# H3_MIDIController_Rev_3_PZBoard.net
KiCad netlist of a schematic drawn in EAGLE
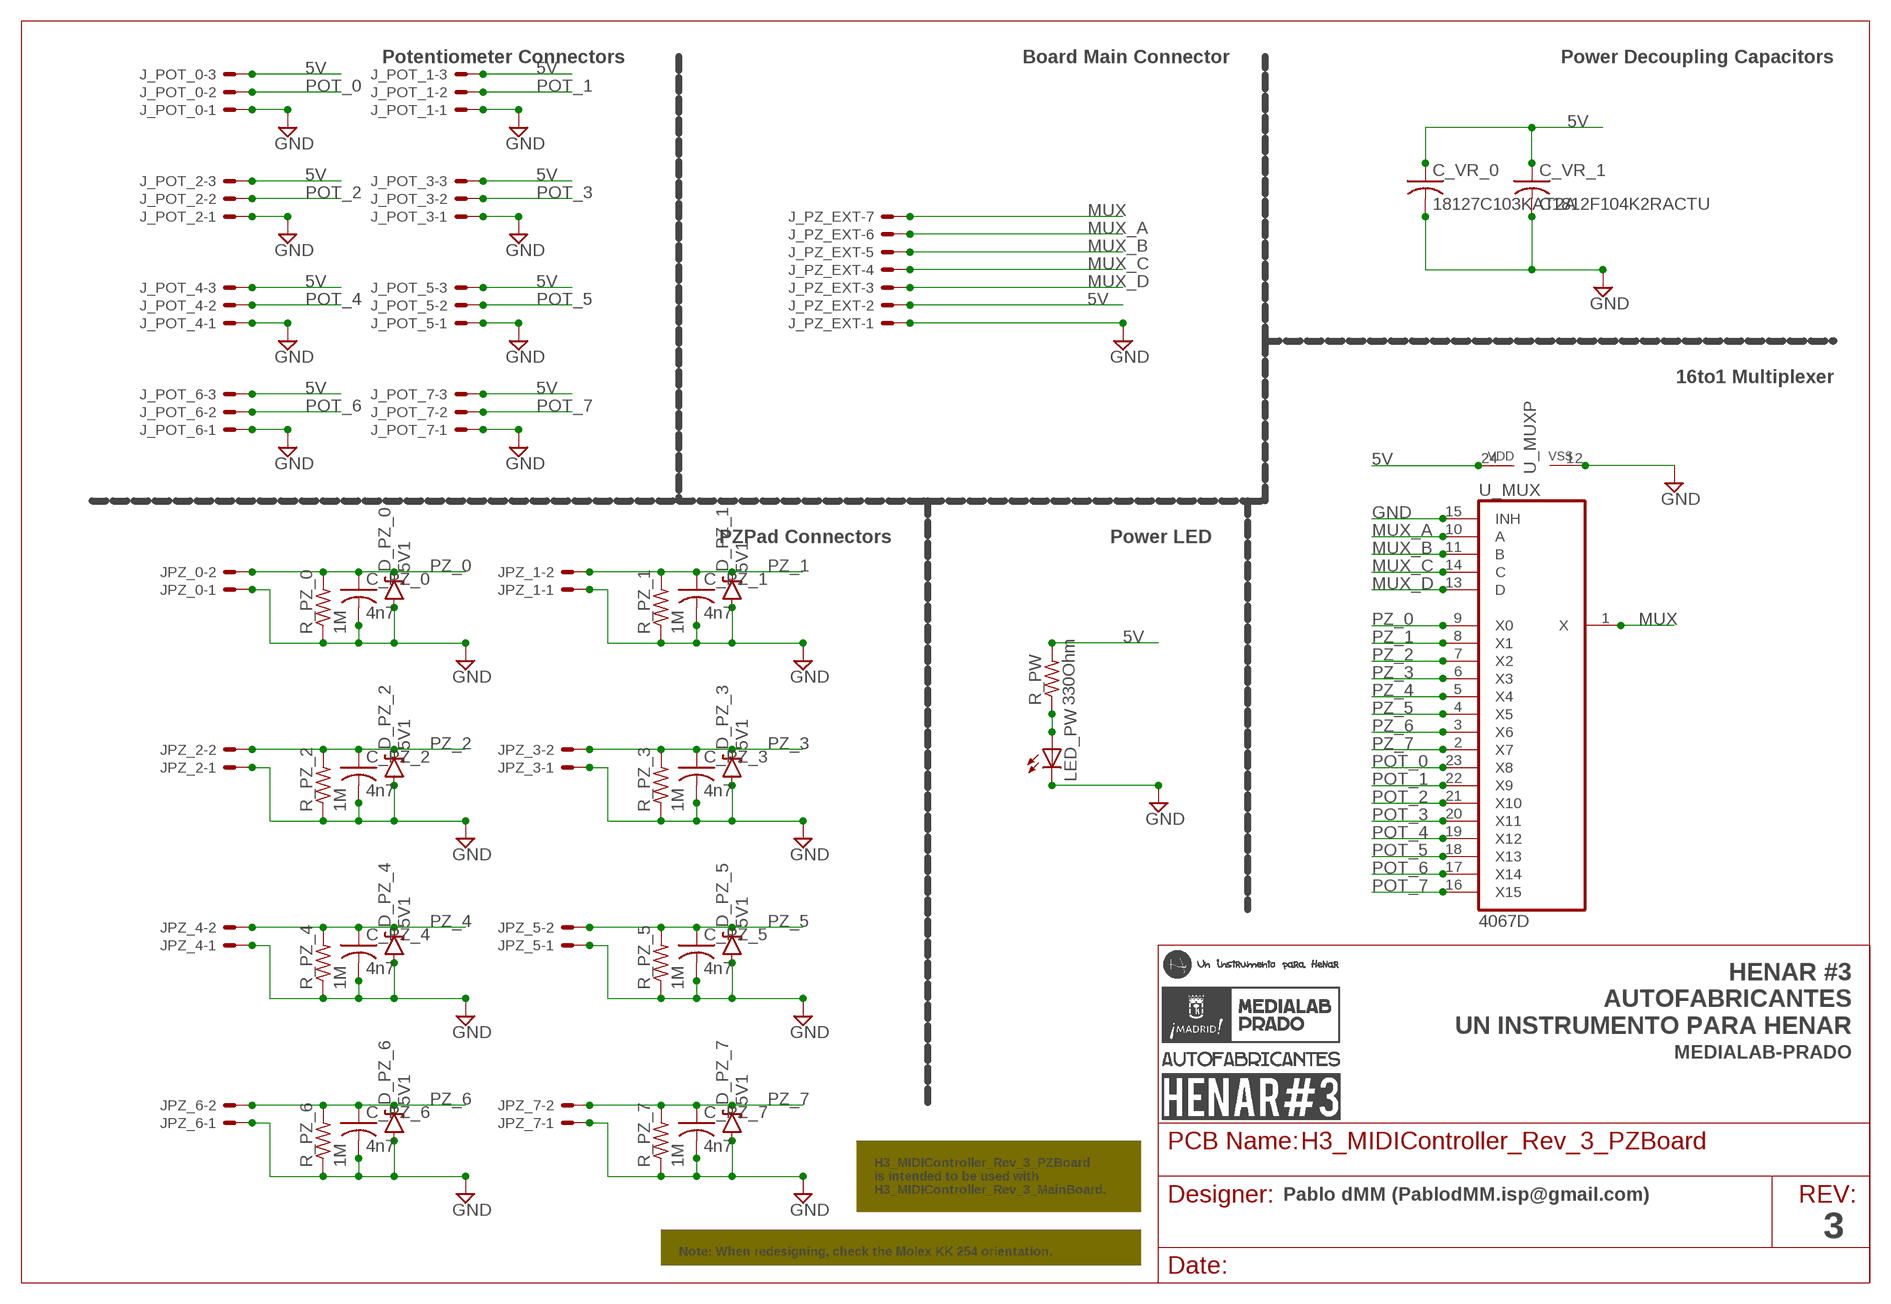
[diagram p0: schematic, sheet 1]

(export (version "E")
  (design (tool "Eeschema 10.0.6"))
  (components
    (comp (ref "C_PZ_0")
      (value "4n7")
      (footprint "eagle-import:C1206")
      (libsource (lib "eagle-import") (part "C-USC1206"))
    )
    (comp (ref "C_PZ_1")
      (value "4n7")
      (footprint "eagle-import:C1206")
      (libsource (lib "eagle-import") (part "C-USC1206"))
    )
    (comp (ref "C_PZ_2")
      (value "4n7")
      (footprint "eagle-import:C1206")
      (libsource (lib "eagle-import") (part "C-USC1206"))
    )
    (comp (ref "C_PZ_3")
      (value "4n7")
      (footprint "eagle-import:C1206")
      (libsource (lib "eagle-import") (part "C-USC1206"))
    )
    (comp (ref "C_PZ_4")
      (value "4n7")
      (footprint "eagle-import:C1206")
      (libsource (lib "eagle-import") (part "C-USC1206"))
    )
    (comp (ref "C_PZ_5")
      (value "4n7")
      (footprint "eagle-import:C1206")
      (libsource (lib "eagle-import") (part "C-USC1206"))
    )
    (comp (ref "C_PZ_6")
      (value "4n7")
      (footprint "eagle-import:C1206")
      (libsource (lib "eagle-import") (part "C-USC1206"))
    )
    (comp (ref "C_PZ_7")
      (value "4n7")
      (footprint "eagle-import:C1206")
      (libsource (lib "eagle-import") (part "C-USC1206"))
    )
    (comp (ref "C_VR_0")
      (value "18127C103KAT2A")
      (footprint "eagle-import:C1812K")
      (libsource (lib "eagle-import") (part "C-USC1812K"))
    )
    (comp (ref "C_VR_1")
      (value "C1812F104K2RACTU")
      (footprint "eagle-import:C1812K")
      (libsource (lib "eagle-import") (part "C-USC1812K"))
    )
    (comp (ref "D_PZ_0")
      (value "5V1")
      (footprint "eagle-import:DIODE-BZT52")
      (libsource (lib "eagle-import") (part "DIODE-ZENER"))
    )
    (comp (ref "D_PZ_1")
      (value "5V1")
      (footprint "eagle-import:DIODE-BZT52")
      (libsource (lib "eagle-import") (part "DIODE-ZENER"))
    )
    (comp (ref "D_PZ_2")
      (value "5V1")
      (footprint "eagle-import:DIODE-BZT52")
      (libsource (lib "eagle-import") (part "DIODE-ZENER"))
    )
    (comp (ref "D_PZ_3")
      (value "5V1")
      (footprint "eagle-import:DIODE-BZT52")
      (libsource (lib "eagle-import") (part "DIODE-ZENER"))
    )
    (comp (ref "D_PZ_4")
      (value "5V1")
      (footprint "eagle-import:DIODE-BZT52")
      (libsource (lib "eagle-import") (part "DIODE-ZENER"))
    )
    (comp (ref "D_PZ_5")
      (value "5V1")
      (footprint "eagle-import:DIODE-BZT52")
      (libsource (lib "eagle-import") (part "DIODE-ZENER"))
    )
    (comp (ref "D_PZ_6")
      (value "5V1")
      (footprint "eagle-import:DIODE-BZT52")
      (libsource (lib "eagle-import") (part "DIODE-ZENER"))
    )
    (comp (ref "D_PZ_7")
      (value "5V1")
      (footprint "eagle-import:DIODE-BZT52")
      (libsource (lib "eagle-import") (part "DIODE-ZENER"))
    )
    (comp (ref "JPZ_0")
      (value "22-05-7028-02")
      (footprint "eagle-import:7395-02")
      (libsource (lib "eagle-import") (part "22-?-0205-7028"))
    )
    (comp (ref "JPZ_1")
      (value "22-05-7028-02")
      (footprint "eagle-import:7395-02")
      (libsource (lib "eagle-import") (part "22-?-0205-7028"))
    )
    (comp (ref "JPZ_2")
      (value "22-05-7028-02")
      (footprint "eagle-import:7395-02")
      (libsource (lib "eagle-import") (part "22-?-0205-7028"))
    )
    (comp (ref "JPZ_3")
      (value "22-05-7028-02")
      (footprint "eagle-import:7395-02")
      (libsource (lib "eagle-import") (part "22-?-0205-7028"))
    )
    (comp (ref "JPZ_4")
      (value "22-05-7028-02")
      (footprint "eagle-import:7395-02")
      (libsource (lib "eagle-import") (part "22-?-0205-7028"))
    )
    (comp (ref "JPZ_5")
      (value "22-05-7028-02")
      (footprint "eagle-import:7395-02")
      (libsource (lib "eagle-import") (part "22-?-0205-7028"))
    )
    (comp (ref "JPZ_6")
      (value "22-05-7028-02")
      (footprint "eagle-import:7395-02")
      (libsource (lib "eagle-import") (part "22-?-0205-7028"))
    )
    (comp (ref "JPZ_7")
      (value "22-05-7028-02")
      (footprint "eagle-import:7395-02")
      (libsource (lib "eagle-import") (part "22-?-0205-7028"))
    )
    (comp (ref "J_POT_0")
      (value "22-05-7038-03")
      (footprint "eagle-import:7395-03")
      (libsource (lib "eagle-import") (part "22-?-0305-7038"))
    )
    (comp (ref "J_POT_1")
      (value "22-05-7038-03")
      (footprint "eagle-import:7395-03")
      (libsource (lib "eagle-import") (part "22-?-0305-7038"))
    )
    (comp (ref "J_POT_2")
      (value "22-05-7038-03")
      (footprint "eagle-import:7395-03")
      (libsource (lib "eagle-import") (part "22-?-0305-7038"))
    )
    (comp (ref "J_POT_3")
      (value "22-05-7038-03")
      (footprint "eagle-import:7395-03")
      (libsource (lib "eagle-import") (part "22-?-0305-7038"))
    )
    (comp (ref "J_POT_4")
      (value "22-05-7038-03")
      (footprint "eagle-import:7395-03")
      (libsource (lib "eagle-import") (part "22-?-0305-7038"))
    )
    (comp (ref "J_POT_5")
      (value "22-05-7038-03")
      (footprint "eagle-import:7395-03")
      (libsource (lib "eagle-import") (part "22-?-0305-7038"))
    )
    (comp (ref "J_POT_6")
      (value "22-05-7038-03")
      (footprint "eagle-import:7395-03")
      (libsource (lib "eagle-import") (part "22-?-0305-7038"))
    )
    (comp (ref "J_POT_7")
      (value "22-05-7038-03")
      (footprint "eagle-import:7395-03")
      (libsource (lib "eagle-import") (part "22-?-0305-7038"))
    )
    (comp (ref "J_PZ_EXT")
      (value "22-05-7078-07")
      (footprint "eagle-import:7395-07")
      (libsource (lib "eagle-import") (part "22-?-0705-7078"))
    )
    (comp (ref "LED_PW")
      (value "LEDSMT1206")
      (footprint "eagle-import:1206")
      (libsource (lib "eagle-import") (part "LEDSMT1206"))
    )
    (comp (ref "R_PW")
      (value "330Ohm")
      (footprint "eagle-import:M1206")
      (libsource (lib "eagle-import") (part "R-US_M1206"))
    )
    (comp (ref "R_PZ_0")
      (value "1M")
      (footprint "eagle-import:M1206")
      (libsource (lib "eagle-import") (part "R-US_M1206"))
    )
    (comp (ref "R_PZ_1")
      (value "1M")
      (footprint "eagle-import:M1206")
      (libsource (lib "eagle-import") (part "R-US_M1206"))
    )
    (comp (ref "R_PZ_2")
      (value "1M")
      (footprint "eagle-import:M1206")
      (libsource (lib "eagle-import") (part "R-US_M1206"))
    )
    (comp (ref "R_PZ_3")
      (value "1M")
      (footprint "eagle-import:M1206")
      (libsource (lib "eagle-import") (part "R-US_M1206"))
    )
    (comp (ref "R_PZ_4")
      (value "1M")
      (footprint "eagle-import:M1206")
      (libsource (lib "eagle-import") (part "R-US_M1206"))
    )
    (comp (ref "R_PZ_5")
      (value "1M")
      (footprint "eagle-import:M1206")
      (libsource (lib "eagle-import") (part "R-US_M1206"))
    )
    (comp (ref "R_PZ_6")
      (value "1M")
      (footprint "eagle-import:M1206")
      (libsource (lib "eagle-import") (part "R-US_M1206"))
    )
    (comp (ref "R_PZ_7")
      (value "1M")
      (footprint "eagle-import:M1206")
      (libsource (lib "eagle-import") (part "R-US_M1206"))
    )
    (comp (ref "U_MUX")
      (value "4067D")
      (footprint "eagle-import:SO24W")
      (libsource (lib "eagle-import") (part "4067D"))
    )
  )
  (nets
    (net (code "1") (name "/5V") (class "Default")
      (node (ref "C_VR_0") (pin "1") (pinfunction "1_1") (pintype "passive"))
      (node (ref "C_VR_1") (pin "1") (pinfunction "1_1") (pintype "passive"))
      (node (ref "J_POT_0") (pin "3") (pinfunction "S_3") (pintype "passive"))
      (node (ref "J_POT_1") (pin "3") (pinfunction "S_3") (pintype "passive"))
      (node (ref "J_POT_2") (pin "3") (pinfunction "S_3") (pintype "passive"))
      (node (ref "J_POT_3") (pin "3") (pinfunction "S_3") (pintype "passive"))
      (node (ref "J_POT_4") (pin "3") (pinfunction "S_3") (pintype "passive"))
      (node (ref "J_POT_5") (pin "3") (pinfunction "S_3") (pintype "passive"))
      (node (ref "J_POT_6") (pin "3") (pinfunction "S_3") (pintype "passive"))
      (node (ref "J_POT_7") (pin "3") (pinfunction "S_3") (pintype "passive"))
      (node (ref "J_PZ_EXT") (pin "2") (pinfunction "S_2") (pintype "passive"))
      (node (ref "R_PW") (pin "2") (pinfunction "2_2") (pintype "passive"))
      (node (ref "U_MUX") (pin "24") (pinfunction "VDD_24") (pintype "power_in"))
    )
    (net (code "2") (name "/MUX") (class "Default")
      (node (ref "J_PZ_EXT") (pin "7") (pinfunction "S_7") (pintype "passive"))
      (node (ref "U_MUX") (pin "1") (pinfunction "X_1") (pintype "output"))
    )
    (net (code "3") (name "/MUX_A") (class "Default")
      (node (ref "J_PZ_EXT") (pin "6") (pinfunction "S_6") (pintype "passive"))
      (node (ref "U_MUX") (pin "10") (pinfunction "A_10") (pintype "input"))
    )
    (net (code "4") (name "/MUX_B") (class "Default")
      (node (ref "J_PZ_EXT") (pin "5") (pinfunction "S_5") (pintype "passive"))
      (node (ref "U_MUX") (pin "11") (pinfunction "B_11") (pintype "input"))
    )
    (net (code "5") (name "/MUX_C") (class "Default")
      (node (ref "J_PZ_EXT") (pin "4") (pinfunction "S_4") (pintype "passive"))
      (node (ref "U_MUX") (pin "14") (pinfunction "C_14") (pintype "input"))
    )
    (net (code "6") (name "/MUX_D") (class "Default")
      (node (ref "J_PZ_EXT") (pin "3") (pinfunction "S_3") (pintype "passive"))
      (node (ref "U_MUX") (pin "13") (pinfunction "D_13") (pintype "input"))
    )
    (net (code "7") (name "/POT_0") (class "Default")
      (node (ref "J_POT_0") (pin "2") (pinfunction "S_2") (pintype "passive"))
      (node (ref "U_MUX") (pin "23") (pinfunction "X8_23") (pintype "input"))
    )
    (net (code "8") (name "/POT_1") (class "Default")
      (node (ref "J_POT_1") (pin "2") (pinfunction "S_2") (pintype "passive"))
      (node (ref "U_MUX") (pin "22") (pinfunction "X9_22") (pintype "input"))
    )
    (net (code "9") (name "/POT_2") (class "Default")
      (node (ref "J_POT_2") (pin "2") (pinfunction "S_2") (pintype "passive"))
      (node (ref "U_MUX") (pin "21") (pinfunction "X10_21") (pintype "input"))
    )
    (net (code "10") (name "/POT_3") (class "Default")
      (node (ref "J_POT_3") (pin "2") (pinfunction "S_2") (pintype "passive"))
      (node (ref "U_MUX") (pin "20") (pinfunction "X11_20") (pintype "input"))
    )
    (net (code "11") (name "/POT_4") (class "Default")
      (node (ref "J_POT_4") (pin "2") (pinfunction "S_2") (pintype "passive"))
      (node (ref "U_MUX") (pin "19") (pinfunction "X12_19") (pintype "input"))
    )
    (net (code "12") (name "/POT_5") (class "Default")
      (node (ref "J_POT_5") (pin "2") (pinfunction "S_2") (pintype "passive"))
      (node (ref "U_MUX") (pin "18") (pinfunction "X13_18") (pintype "input"))
    )
    (net (code "13") (name "/POT_6") (class "Default")
      (node (ref "J_POT_6") (pin "2") (pinfunction "S_2") (pintype "passive"))
      (node (ref "U_MUX") (pin "17") (pinfunction "X14_17") (pintype "input"))
    )
    (net (code "14") (name "/POT_7") (class "Default")
      (node (ref "J_POT_7") (pin "2") (pinfunction "S_2") (pintype "passive"))
      (node (ref "U_MUX") (pin "16") (pinfunction "X15_16") (pintype "input"))
    )
    (net (code "15") (name "/PZ_0") (class "Default")
      (node (ref "C_PZ_0") (pin "1") (pinfunction "1_1") (pintype "passive"))
      (node (ref "D_PZ_0") (pin "C") (pinfunction "C_C") (pintype "passive"))
      (node (ref "JPZ_0") (pin "2") (pinfunction "S_2") (pintype "passive"))
      (node (ref "R_PZ_0") (pin "2") (pinfunction "2_2") (pintype "passive"))
      (node (ref "U_MUX") (pin "9") (pinfunction "X0_9") (pintype "input"))
    )
    (net (code "16") (name "/PZ_1") (class "Default")
      (node (ref "C_PZ_1") (pin "1") (pinfunction "1_1") (pintype "passive"))
      (node (ref "D_PZ_1") (pin "C") (pinfunction "C_C") (pintype "passive"))
      (node (ref "JPZ_1") (pin "2") (pinfunction "S_2") (pintype "passive"))
      (node (ref "R_PZ_1") (pin "2") (pinfunction "2_2") (pintype "passive"))
      (node (ref "U_MUX") (pin "8") (pinfunction "X1_8") (pintype "input"))
    )
    (net (code "17") (name "/PZ_2") (class "Default")
      (node (ref "C_PZ_2") (pin "1") (pinfunction "1_1") (pintype "passive"))
      (node (ref "D_PZ_2") (pin "C") (pinfunction "C_C") (pintype "passive"))
      (node (ref "JPZ_2") (pin "2") (pinfunction "S_2") (pintype "passive"))
      (node (ref "R_PZ_2") (pin "2") (pinfunction "2_2") (pintype "passive"))
      (node (ref "U_MUX") (pin "7") (pinfunction "X2_7") (pintype "input"))
    )
    (net (code "18") (name "/PZ_3") (class "Default")
      (node (ref "C_PZ_3") (pin "1") (pinfunction "1_1") (pintype "passive"))
      (node (ref "D_PZ_3") (pin "C") (pinfunction "C_C") (pintype "passive"))
      (node (ref "JPZ_3") (pin "2") (pinfunction "S_2") (pintype "passive"))
      (node (ref "R_PZ_3") (pin "2") (pinfunction "2_2") (pintype "passive"))
      (node (ref "U_MUX") (pin "6") (pinfunction "X3_6") (pintype "input"))
    )
    (net (code "19") (name "/PZ_4") (class "Default")
      (node (ref "C_PZ_4") (pin "1") (pinfunction "1_1") (pintype "passive"))
      (node (ref "D_PZ_4") (pin "C") (pinfunction "C_C") (pintype "passive"))
      (node (ref "JPZ_4") (pin "2") (pinfunction "S_2") (pintype "passive"))
      (node (ref "R_PZ_4") (pin "2") (pinfunction "2_2") (pintype "passive"))
      (node (ref "U_MUX") (pin "5") (pinfunction "X4_5") (pintype "input"))
    )
    (net (code "20") (name "/PZ_5") (class "Default")
      (node (ref "C_PZ_5") (pin "1") (pinfunction "1_1") (pintype "passive"))
      (node (ref "D_PZ_5") (pin "C") (pinfunction "C_C") (pintype "passive"))
      (node (ref "JPZ_5") (pin "2") (pinfunction "S_2") (pintype "passive"))
      (node (ref "R_PZ_5") (pin "2") (pinfunction "2_2") (pintype "passive"))
      (node (ref "U_MUX") (pin "4") (pinfunction "X5_4") (pintype "input"))
    )
    (net (code "21") (name "/PZ_6") (class "Default")
      (node (ref "C_PZ_6") (pin "1") (pinfunction "1_1") (pintype "passive"))
      (node (ref "D_PZ_6") (pin "C") (pinfunction "C_C") (pintype "passive"))
      (node (ref "JPZ_6") (pin "2") (pinfunction "S_2") (pintype "passive"))
      (node (ref "R_PZ_6") (pin "2") (pinfunction "2_2") (pintype "passive"))
      (node (ref "U_MUX") (pin "3") (pinfunction "X6_3") (pintype "input"))
    )
    (net (code "22") (name "/PZ_7") (class "Default")
      (node (ref "C_PZ_7") (pin "1") (pinfunction "1_1") (pintype "passive"))
      (node (ref "D_PZ_7") (pin "C") (pinfunction "C_C") (pintype "passive"))
      (node (ref "JPZ_7") (pin "2") (pinfunction "S_2") (pintype "passive"))
      (node (ref "R_PZ_7") (pin "2") (pinfunction "2_2") (pintype "passive"))
      (node (ref "U_MUX") (pin "2") (pinfunction "X7_2") (pintype "input"))
    )
    (net (code "23") (name "GND") (class "Default")
      (node (ref "C_PZ_0") (pin "2") (pinfunction "2_2") (pintype "passive"))
      (node (ref "C_PZ_1") (pin "2") (pinfunction "2_2") (pintype "passive"))
      (node (ref "C_PZ_2") (pin "2") (pinfunction "2_2") (pintype "passive"))
      (node (ref "C_PZ_3") (pin "2") (pinfunction "2_2") (pintype "passive"))
      (node (ref "C_PZ_4") (pin "2") (pinfunction "2_2") (pintype "passive"))
      (node (ref "C_PZ_5") (pin "2") (pinfunction "2_2") (pintype "passive"))
      (node (ref "C_PZ_6") (pin "2") (pinfunction "2_2") (pintype "passive"))
      (node (ref "C_PZ_7") (pin "2") (pinfunction "2_2") (pintype "passive"))
      (node (ref "C_VR_0") (pin "2") (pinfunction "2_2") (pintype "passive"))
      (node (ref "C_VR_1") (pin "2") (pinfunction "2_2") (pintype "passive"))
      (node (ref "D_PZ_0") (pin "A") (pinfunction "A_A") (pintype "passive"))
      (node (ref "D_PZ_1") (pin "A") (pinfunction "A_A") (pintype "passive"))
      (node (ref "D_PZ_2") (pin "A") (pinfunction "A_A") (pintype "passive"))
      (node (ref "D_PZ_3") (pin "A") (pinfunction "A_A") (pintype "passive"))
      (node (ref "D_PZ_4") (pin "A") (pinfunction "A_A") (pintype "passive"))
      (node (ref "D_PZ_5") (pin "A") (pinfunction "A_A") (pintype "passive"))
      (node (ref "D_PZ_6") (pin "A") (pinfunction "A_A") (pintype "passive"))
      (node (ref "D_PZ_7") (pin "A") (pinfunction "A_A") (pintype "passive"))
      (node (ref "JPZ_0") (pin "1") (pinfunction "S_1") (pintype "passive"))
      (node (ref "JPZ_1") (pin "1") (pinfunction "S_1") (pintype "passive"))
      (node (ref "JPZ_2") (pin "1") (pinfunction "S_1") (pintype "passive"))
      (node (ref "JPZ_3") (pin "1") (pinfunction "S_1") (pintype "passive"))
      (node (ref "JPZ_4") (pin "1") (pinfunction "S_1") (pintype "passive"))
      (node (ref "JPZ_5") (pin "1") (pinfunction "S_1") (pintype "passive"))
      (node (ref "JPZ_6") (pin "1") (pinfunction "S_1") (pintype "passive"))
      (node (ref "JPZ_7") (pin "1") (pinfunction "S_1") (pintype "passive"))
      (node (ref "J_POT_0") (pin "1") (pinfunction "S_1") (pintype "passive"))
      (node (ref "J_POT_1") (pin "1") (pinfunction "S_1") (pintype "passive"))
      (node (ref "J_POT_2") (pin "1") (pinfunction "S_1") (pintype "passive"))
      (node (ref "J_POT_3") (pin "1") (pinfunction "S_1") (pintype "passive"))
      (node (ref "J_POT_4") (pin "1") (pinfunction "S_1") (pintype "passive"))
      (node (ref "J_POT_5") (pin "1") (pinfunction "S_1") (pintype "passive"))
      (node (ref "J_POT_6") (pin "1") (pinfunction "S_1") (pintype "passive"))
      (node (ref "J_POT_7") (pin "1") (pinfunction "S_1") (pintype "passive"))
      (node (ref "J_PZ_EXT") (pin "1") (pinfunction "S_1") (pintype "passive"))
      (node (ref "LED_PW") (pin "C") (pinfunction "C_C") (pintype "passive"))
      (node (ref "R_PZ_0") (pin "1") (pinfunction "1_1") (pintype "passive"))
      (node (ref "R_PZ_1") (pin "1") (pinfunction "1_1") (pintype "passive"))
      (node (ref "R_PZ_2") (pin "1") (pinfunction "1_1") (pintype "passive"))
      (node (ref "R_PZ_3") (pin "1") (pinfunction "1_1") (pintype "passive"))
      (node (ref "R_PZ_4") (pin "1") (pinfunction "1_1") (pintype "passive"))
      (node (ref "R_PZ_5") (pin "1") (pinfunction "1_1") (pintype "passive"))
      (node (ref "R_PZ_6") (pin "1") (pinfunction "1_1") (pintype "passive"))
      (node (ref "R_PZ_7") (pin "1") (pinfunction "1_1") (pintype "passive"))
      (node (ref "U_MUX") (pin "12") (pinfunction "VSS_12") (pintype "power_in"))
      (node (ref "U_MUX") (pin "15") (pinfunction "INH_15") (pintype "input"))
    )
    (net (code "24") (name "Net-(LED_PW-PadA)") (class "Default")
      (node (ref "LED_PW") (pin "A") (pinfunction "A_A") (pintype "passive"))
      (node (ref "R_PW") (pin "1") (pinfunction "1_1") (pintype "passive"))
    )
  )
)
